# sch.net
KiCad netlist of a schematic drawn in Altium Designer
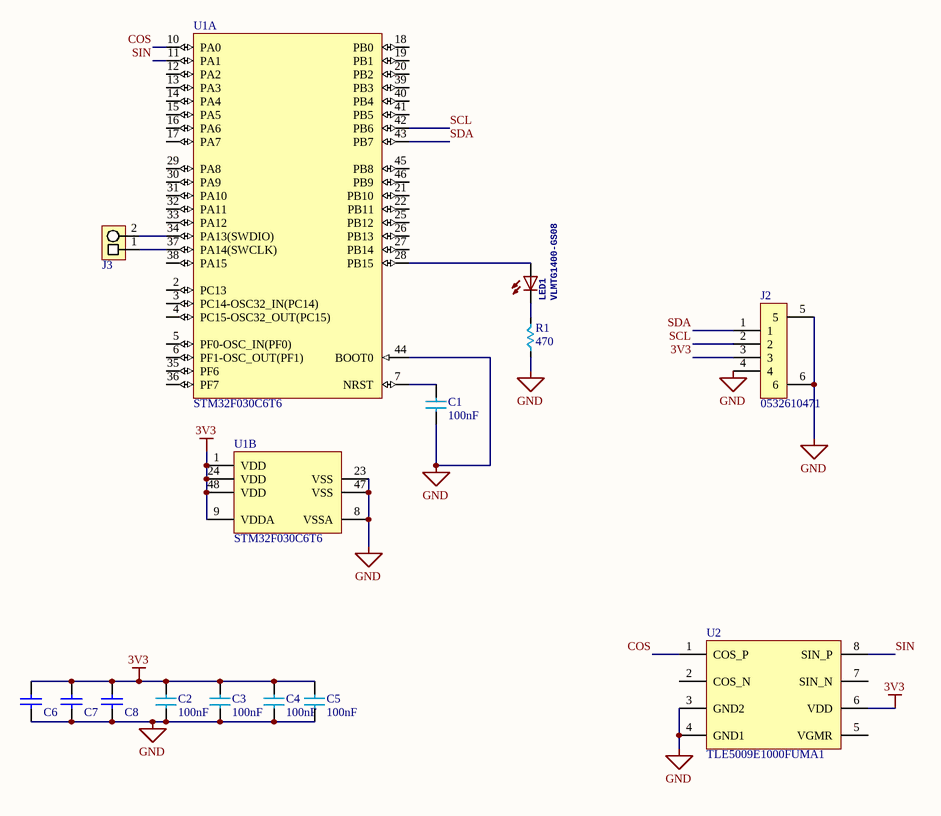
[diagram p0: sch.SchDoc]

(export (version "E")
  (design (tool "Eeschema 10.0.6"))
  (components
    (comp (ref "C1")
      (value "100nF")
      (footprint "c0402")
      (fields
        (field (name "MANUFACTURER") "Samsung")
        (field (name "MANUFACTURER PART NUMBER") "CL05F104ZO5NNNC")
        (field (name "TOLERANCE") "80%")
      )
      (libsource (lib "mag-encoder-uart") (part "C0402-100nF"))
    )
    (comp (ref "C2")
      (value "100nF")
      (footprint "c0402")
      (fields
        (field (name "MANUFACTURER") "Samsung")
        (field (name "MANUFACTURER PART NUMBER") "CL05F104ZO5NNNC")
        (field (name "TOLERANCE") "80%")
      )
      (libsource (lib "mag-encoder-uart") (part "C0402-100nF"))
    )
    (comp (ref "C3")
      (value "100nF")
      (footprint "c0402")
      (fields
        (field (name "MANUFACTURER") "Samsung")
        (field (name "MANUFACTURER PART NUMBER") "CL05F104ZO5NNNC")
        (field (name "TOLERANCE") "80%")
      )
      (libsource (lib "mag-encoder-uart") (part "C0402-100nF"))
    )
    (comp (ref "C4")
      (value "100nF")
      (footprint "c0402")
      (fields
        (field (name "MANUFACTURER") "Samsung")
        (field (name "MANUFACTURER PART NUMBER") "CL05F104ZO5NNNC")
        (field (name "TOLERANCE") "80%")
      )
      (libsource (lib "mag-encoder-uart") (part "C0402-100nF"))
    )
    (comp (ref "C5")
      (value "100nF")
      (footprint "c0402")
      (fields
        (field (name "MANUFACTURER") "Samsung")
        (field (name "MANUFACTURER PART NUMBER") "CL05F104ZO5NNNC")
        (field (name "TOLERANCE") "80%")
      )
      (libsource (lib "mag-encoder-uart") (part "C0402-100nF"))
    )
    (comp (ref "C6")
      (value "4.7uF")
      (footprint "C0603")
      (description "Cap Ceramic 4.7uF 6.3VDC X5R 10% SMD 0603 Paper T/R")
      (fields
        (field (name "MANUFACTURER") "Samsung")
        (field (name "MANUFACTURER PART NUMBER") "CL10A475KQ8NNNC")
      )
      (libsource (lib "mag-encoder-uart") (part "C0603-4.7uF"))
    )
    (comp (ref "C7")
      (value "4.7uF")
      (footprint "C0603")
      (description "Cap Ceramic 4.7uF 6.3VDC X5R 10% SMD 0603 Paper T/R")
      (fields
        (field (name "MANUFACTURER") "Samsung")
        (field (name "MANUFACTURER PART NUMBER") "CL10A475KQ8NNNC")
      )
      (libsource (lib "mag-encoder-uart") (part "C0603-4.7uF"))
    )
    (comp (ref "C8")
      (value "4.7uF")
      (footprint "C0603")
      (description "Cap Ceramic 4.7uF 6.3VDC X5R 10% SMD 0603 Paper T/R")
      (fields
        (field (name "MANUFACTURER") "Samsung")
        (field (name "MANUFACTURER PART NUMBER") "CL10A475KQ8NNNC")
      )
      (libsource (lib "mag-encoder-uart") (part "C0603-4.7uF"))
    )
    (comp (ref "J2")
      (value "0532610471")
      (footprint "0532610471")
      (description "Headers & Wire Housings 1.25MM HDR 4 CKT Right-Angle")
      (fields (field (name "MANUFACTURER") "Molex") (field (name "MANUFACTURER PART NUMBER") "53261-0471"))
      (libsource (lib "mag-encoder-uart") (part "0532610471"))
    )
    (comp (ref "J3")
      (value "PIN-DUAL")
      (footprint "PAD-DOUBLE")
      (libsource (lib "mag-encoder-uart") (part "PIN-DUAL"))
    )
    (comp (ref "LED1")
      (value "VLMTG1400-GS08")
      (footprint "LED_0603")
      (description "LED GREEN 0603 SMD")
      (fields (field (name "MANUFACTURER") "Vishay"))
      (libsource (lib "mag-encoder-uart") (part "VLMTG1400-GS08"))
    )
    (comp (ref "R1")
      (value "470")
      (footprint "R0402")
      (description "RES 680 OHM 5% 1/16W 0402")
      (fields
        (field (name "MANUFACTURER") "Yageo")
        (field (name "MANUFACTURER PART NUMBER") "RC0402JR-07470RL")
      )
      (libsource (lib "mag-encoder-uart") (part "RC0402JR-07470RL"))
    )
    (comp (ref "U1")
      (value "STM32F030C6T6")
      (footprint "LQFP48")
      (fields (field (name "MANUFACTURER") "STMicroelectronics"))
      (libsource (lib "mag-encoder-uart") (part "STM32F030C6T6"))
    )
    (comp (ref "U2")
      (value "TLE5009E1000FUMA1")
      (footprint "SOIC127P600X175-8L")
      (description "RotaryPosition Sensor 5.5V Automotive 8-Pin DSO Tape and Reel")
      (fields (field (name "MANUFACTURER") "Infineon"))
      (libsource (lib "mag-encoder-uart") (part "TLE5009E1000FUMA1"))
    )
  )
  (nets
    (net (code "1") (name "/COS") (class "Default")
      (node (ref "U1") (pin "10") (pinfunction "PA0_10") (pintype "bidirectional"))
      (node (ref "U2") (pin "1") (pinfunction "COS_P_1") (pintype "passive"))
    )
    (net (code "2") (name "/SCL") (class "Default")
      (node (ref "J2") (pin "2") (pinfunction "2_2") (pintype "power_in"))
      (node (ref "U1") (pin "42") (pinfunction "PB6_42") (pintype "bidirectional"))
    )
    (net (code "3") (name "/SDA") (class "Default")
      (node (ref "J2") (pin "1") (pinfunction "1_1") (pintype "power_in"))
      (node (ref "U1") (pin "43") (pinfunction "PB7_43") (pintype "bidirectional"))
    )
    (net (code "4") (name "/SIN") (class "Default")
      (node (ref "U1") (pin "11") (pinfunction "PA1_11") (pintype "bidirectional"))
      (node (ref "U2") (pin "8") (pinfunction "SIN_P_8") (pintype "passive"))
    )
    (net (code "5") (name "3V3") (class "Default")
      (node (ref "C2") (pin "1") (pinfunction "1_1") (pintype "passive"))
      (node (ref "C3") (pin "1") (pinfunction "1_1") (pintype "passive"))
      (node (ref "C4") (pin "1") (pinfunction "1_1") (pintype "passive"))
      (node (ref "C5") (pin "1") (pinfunction "1_1") (pintype "passive"))
      (node (ref "C6") (pin "2") (pinfunction "2_2") (pintype "passive"))
      (node (ref "C7") (pin "2") (pinfunction "2_2") (pintype "passive"))
      (node (ref "C8") (pin "2") (pinfunction "2_2") (pintype "passive"))
      (node (ref "J2") (pin "3") (pinfunction "3_3") (pintype "power_in"))
      (node (ref "U1") (pin "1") (pinfunction "VDD_1") (pintype "power_in"))
      (node (ref "U1") (pin "24") (pinfunction "VDD_24") (pintype "power_in"))
      (node (ref "U1") (pin "48") (pinfunction "VDD_48") (pintype "power_in"))
      (node (ref "U1") (pin "9") (pinfunction "VDDA_9") (pintype "power_in"))
      (node (ref "U2") (pin "6") (pinfunction "VDD_6") (pintype "passive"))
    )
    (net (code "6") (name "GND") (class "Default")
      (node (ref "C1") (pin "2") (pinfunction "2_2") (pintype "passive"))
      (node (ref "C2") (pin "2") (pinfunction "2_2") (pintype "passive"))
      (node (ref "C3") (pin "2") (pinfunction "2_2") (pintype "passive"))
      (node (ref "C4") (pin "2") (pinfunction "2_2") (pintype "passive"))
      (node (ref "C5") (pin "2") (pinfunction "2_2") (pintype "passive"))
      (node (ref "C6") (pin "1") (pinfunction "1_1") (pintype "passive"))
      (node (ref "C7") (pin "1") (pinfunction "1_1") (pintype "passive"))
      (node (ref "C8") (pin "1") (pinfunction "1_1") (pintype "passive"))
      (node (ref "J2") (pin "4") (pinfunction "4_4") (pintype "power_in"))
      (node (ref "J2") (pin "5") (pinfunction "5_5") (pintype "power_in"))
      (node (ref "J2") (pin "6") (pinfunction "6_6") (pintype "power_in"))
      (node (ref "R1") (pin "2") (pinfunction "2_2") (pintype "passive"))
      (node (ref "U1") (pin "23") (pinfunction "VSS_23") (pintype "power_in"))
      (node (ref "U1") (pin "44") (pinfunction "BOOT0_44") (pintype "input"))
      (node (ref "U1") (pin "47") (pinfunction "VSS_47") (pintype "power_in"))
      (node (ref "U1") (pin "8") (pinfunction "VSSA_8") (pintype "power_in"))
      (node (ref "U2") (pin "3") (pinfunction "GND2_3") (pintype "passive"))
      (node (ref "U2") (pin "4") (pinfunction "GND1_4") (pintype "passive"))
    )
    (net (code "7") (name "Net-(LED1-PadC)") (class "Default")
      (node (ref "LED1") (pin "C") (pinfunction "C_C") (pintype "passive"))
      (node (ref "R1") (pin "1") (pinfunction "1_1") (pintype "passive"))
    )
    (net (code "8") (name "Net-(U1A-NRST)") (class "Default")
      (node (ref "C1") (pin "1") (pinfunction "1_1") (pintype "passive"))
      (node (ref "U1") (pin "7") (pinfunction "NRST_7") (pintype "bidirectional"))
    )
    (net (code "9") (name "Net-(U1A-PA13(SWDIO))") (class "Default")
      (node (ref "J3") (pin "2") (pinfunction "2_2") (pintype "passive"))
      (node (ref "U1") (pin "34") (pinfunction "PA13(SWDIO)_34") (pintype "bidirectional"))
    )
    (net (code "10") (name "Net-(U1A-PA14(SWCLK))") (class "Default")
      (node (ref "J3") (pin "1") (pinfunction "1_1") (pintype "passive"))
      (node (ref "U1") (pin "37") (pinfunction "PA14(SWCLK)_37") (pintype "bidirectional"))
    )
    (net (code "11") (name "Net-(U1A-PB15)") (class "Default")
      (node (ref "LED1") (pin "A") (pinfunction "A_A") (pintype "passive"))
      (node (ref "U1") (pin "28") (pinfunction "PB15_28") (pintype "bidirectional"))
    )
    (net (code "12") (name "unconnected-(U1A-PA2-Pad12)") (class "Default")
      (node (ref "U1") (pin "12") (pinfunction "PA2_12") (pintype "bidirectional"))
    )
    (net (code "13") (name "unconnected-(U1A-PA3-Pad13)") (class "Default")
      (node (ref "U1") (pin "13") (pinfunction "PA3_13") (pintype "bidirectional"))
    )
    (net (code "14") (name "unconnected-(U1A-PA4-Pad14)") (class "Default")
      (node (ref "U1") (pin "14") (pinfunction "PA4_14") (pintype "bidirectional"))
    )
    (net (code "15") (name "unconnected-(U1A-PA5-Pad15)") (class "Default")
      (node (ref "U1") (pin "15") (pinfunction "PA5_15") (pintype "bidirectional"))
    )
    (net (code "16") (name "unconnected-(U1A-PA6-Pad16)") (class "Default")
      (node (ref "U1") (pin "16") (pinfunction "PA6_16") (pintype "bidirectional"))
    )
    (net (code "17") (name "unconnected-(U1A-PA7-Pad17)") (class "Default")
      (node (ref "U1") (pin "17") (pinfunction "PA7_17") (pintype "bidirectional"))
    )
    (net (code "18") (name "unconnected-(U1A-PA8-Pad29)") (class "Default")
      (node (ref "U1") (pin "29") (pinfunction "PA8_29") (pintype "bidirectional"))
    )
    (net (code "19") (name "unconnected-(U1A-PA9-Pad30)") (class "Default")
      (node (ref "U1") (pin "30") (pinfunction "PA9_30") (pintype "bidirectional"))
    )
    (net (code "20") (name "unconnected-(U1A-PA10-Pad31)") (class "Default")
      (node (ref "U1") (pin "31") (pinfunction "PA10_31") (pintype "bidirectional"))
    )
    (net (code "21") (name "unconnected-(U1A-PA11-Pad32)") (class "Default")
      (node (ref "U1") (pin "32") (pinfunction "PA11_32") (pintype "bidirectional"))
    )
    (net (code "22") (name "unconnected-(U1A-PA12-Pad33)") (class "Default")
      (node (ref "U1") (pin "33") (pinfunction "PA12_33") (pintype "bidirectional"))
    )
    (net (code "23") (name "unconnected-(U1A-PA15-Pad38)") (class "Default")
      (node (ref "U1") (pin "38") (pinfunction "PA15_38") (pintype "bidirectional"))
    )
    (net (code "24") (name "unconnected-(U1A-PB0-Pad18)") (class "Default")
      (node (ref "U1") (pin "18") (pinfunction "PB0_18") (pintype "bidirectional"))
    )
    (net (code "25") (name "unconnected-(U1A-PB1-Pad19)") (class "Default")
      (node (ref "U1") (pin "19") (pinfunction "PB1_19") (pintype "bidirectional"))
    )
    (net (code "26") (name "unconnected-(U1A-PB2-Pad20)") (class "Default")
      (node (ref "U1") (pin "20") (pinfunction "PB2_20") (pintype "bidirectional"))
    )
    (net (code "27") (name "unconnected-(U1A-PB3-Pad39)") (class "Default")
      (node (ref "U1") (pin "39") (pinfunction "PB3_39") (pintype "bidirectional"))
    )
    (net (code "28") (name "unconnected-(U1A-PB4-Pad40)") (class "Default")
      (node (ref "U1") (pin "40") (pinfunction "PB4_40") (pintype "bidirectional"))
    )
    (net (code "29") (name "unconnected-(U1A-PB5-Pad41)") (class "Default")
      (node (ref "U1") (pin "41") (pinfunction "PB5_41") (pintype "bidirectional"))
    )
    (net (code "30") (name "unconnected-(U1A-PB8-Pad45)") (class "Default")
      (node (ref "U1") (pin "45") (pinfunction "PB8_45") (pintype "bidirectional"))
    )
    (net (code "31") (name "unconnected-(U1A-PB9-Pad46)") (class "Default")
      (node (ref "U1") (pin "46") (pinfunction "PB9_46") (pintype "bidirectional"))
    )
    (net (code "32") (name "unconnected-(U1A-PB10-Pad21)") (class "Default")
      (node (ref "U1") (pin "21") (pinfunction "PB10_21") (pintype "bidirectional"))
    )
    (net (code "33") (name "unconnected-(U1A-PB11-Pad22)") (class "Default")
      (node (ref "U1") (pin "22") (pinfunction "PB11_22") (pintype "bidirectional"))
    )
    (net (code "34") (name "unconnected-(U1A-PB12-Pad25)") (class "Default")
      (node (ref "U1") (pin "25") (pinfunction "PB12_25") (pintype "bidirectional"))
    )
    (net (code "35") (name "unconnected-(U1A-PB13-Pad26)") (class "Default")
      (node (ref "U1") (pin "26") (pinfunction "PB13_26") (pintype "bidirectional"))
    )
    (net (code "36") (name "unconnected-(U1A-PB14-Pad27)") (class "Default")
      (node (ref "U1") (pin "27") (pinfunction "PB14_27") (pintype "bidirectional"))
    )
    (net (code "37") (name "unconnected-(U1A-PC13-Pad2)") (class "Default")
      (node (ref "U1") (pin "2") (pinfunction "PC13_2") (pintype "bidirectional"))
    )
    (net (code "38") (name "unconnected-(U1A-PC14-OSC32_IN(PC14)-Pad3)") (class "Default")
      (node (ref "U1") (pin "3") (pinfunction "PC14-OSC32_IN(PC14)_3") (pintype "bidirectional"))
    )
    (net (code "39") (name "unconnected-(U1A-PC15-OSC32_OUT(PC15)-Pad4)") (class "Default")
      (node (ref "U1") (pin "4") (pinfunction "PC15-OSC32_OUT(PC15)_4") (pintype "bidirectional"))
    )
    (net (code "40") (name "unconnected-(U1A-PF0-OSC_IN(PF0)-Pad5)") (class "Default")
      (node (ref "U1") (pin "5") (pinfunction "PF0-OSC_IN(PF0)_5") (pintype "bidirectional"))
    )
    (net (code "41") (name "unconnected-(U1A-PF1-OSC_OUT(PF1)-Pad6)") (class "Default")
      (node (ref "U1") (pin "6") (pinfunction "PF1-OSC_OUT(PF1)_6") (pintype "bidirectional"))
    )
    (net (code "42") (name "unconnected-(U1A-PF6-Pad35)") (class "Default")
      (node (ref "U1") (pin "35") (pinfunction "PF6_35") (pintype "bidirectional"))
    )
    (net (code "43") (name "unconnected-(U1A-PF7-Pad36)") (class "Default")
      (node (ref "U1") (pin "36") (pinfunction "PF7_36") (pintype "bidirectional"))
    )
    (net (code "44") (name "unconnected-(U2-COS_N-Pad2)") (class "Default")
      (node (ref "U2") (pin "2") (pinfunction "COS_N_2") (pintype "passive"))
    )
    (net (code "45") (name "unconnected-(U2-SIN_N-Pad7)") (class "Default")
      (node (ref "U2") (pin "7") (pinfunction "SIN_N_7") (pintype "passive"))
    )
    (net (code "46") (name "unconnected-(U2-VGMR-Pad5)") (class "Default")
      (node (ref "U2") (pin "5") (pinfunction "VGMR_5") (pintype "passive"))
    )
  )
)
